# BluetoothAUX.net
KiCad netlist of a schematic drawn in EAGLE
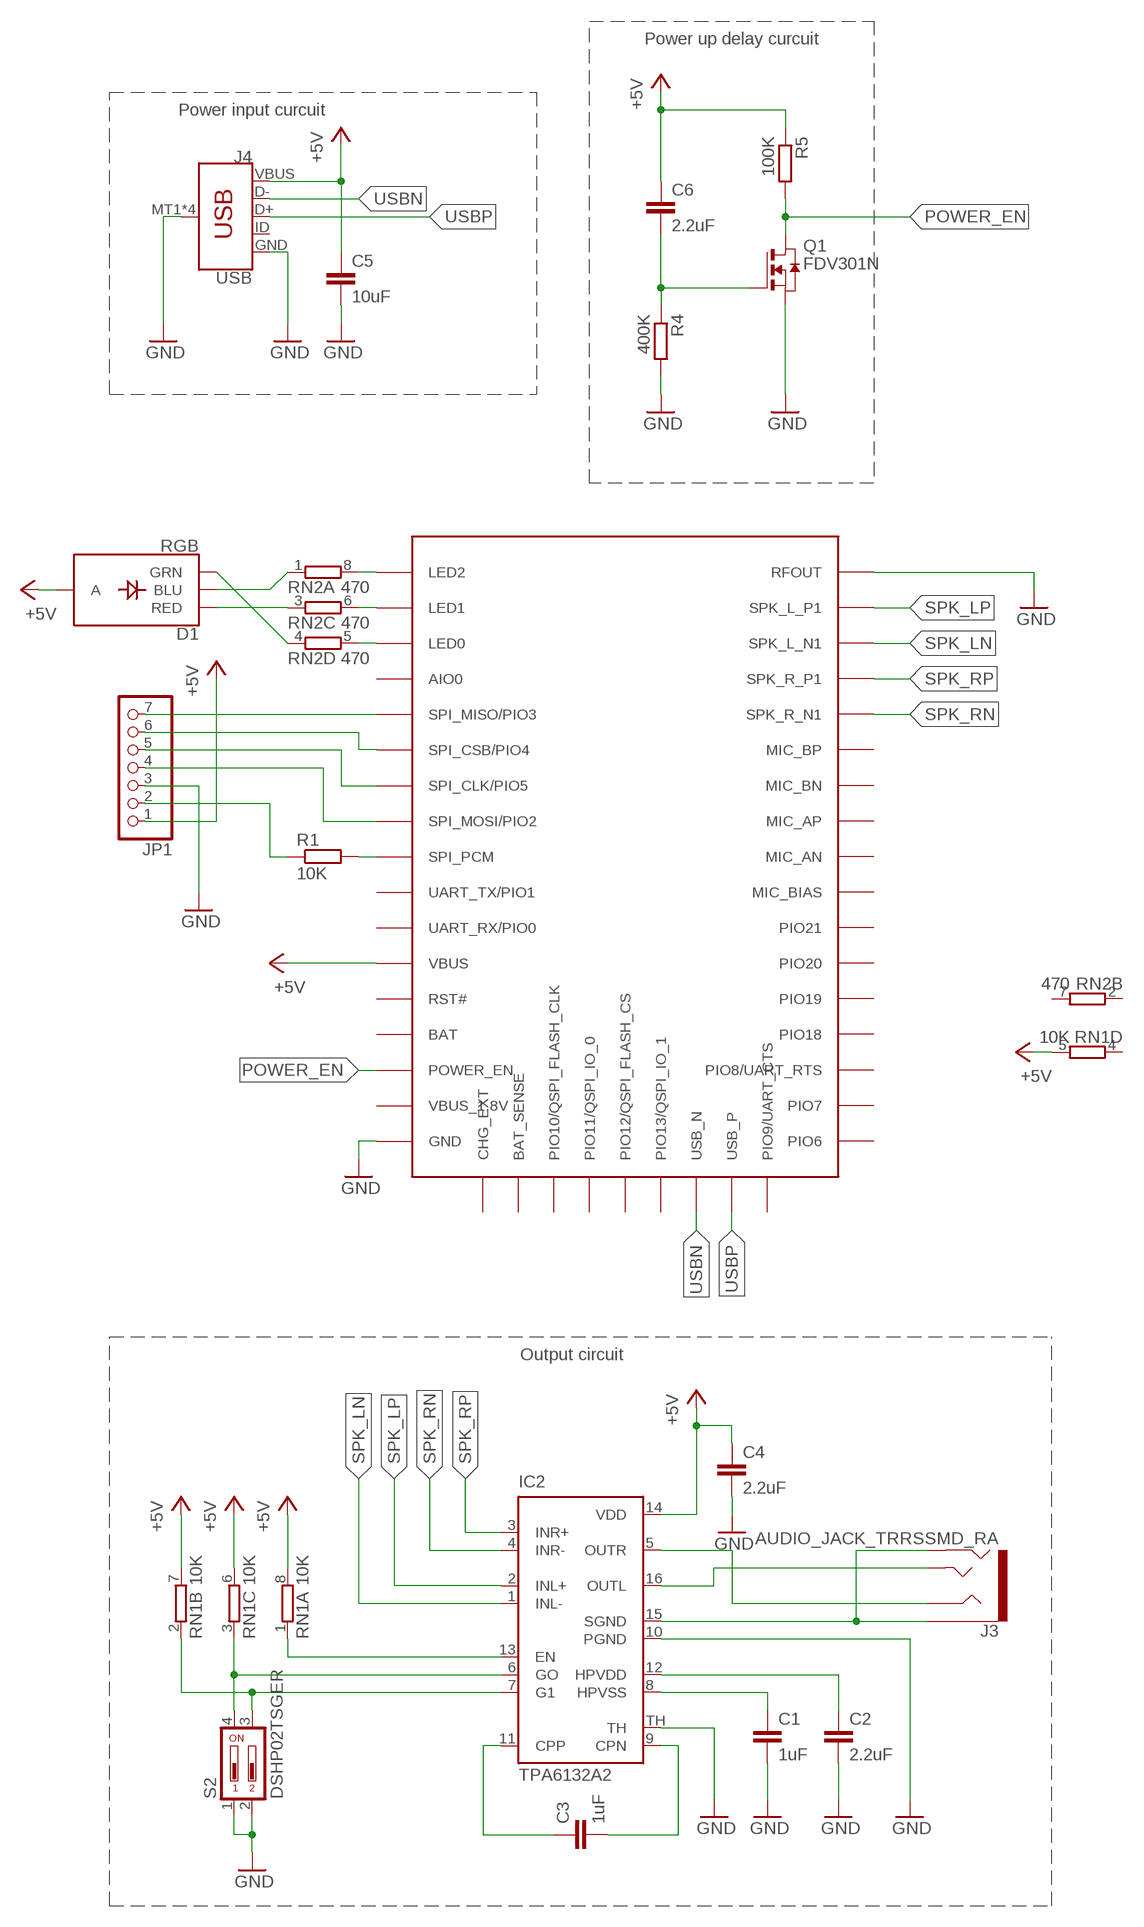
[diagram p0: schematic, sheet 1]

(export (version "E")
  (design (tool "Eeschema 10.0.6"))
  (components
    (comp (ref "C1")
      (value "1uF")
      (footprint "eagle-import:C0603")
      (libsource (lib "eagle-import") (part "resistor_348_C-EUC0603"))
    )
    (comp (ref "C2")
      (value "2.2uF")
      (footprint "eagle-import:C0603")
      (libsource (lib "eagle-import") (part "resistor_348_C-EUC0603"))
    )
    (comp (ref "C3")
      (value "1uF")
      (footprint "eagle-import:C0603")
      (libsource (lib "eagle-import") (part "resistor_348_C-EUC0603"))
    )
    (comp (ref "C4")
      (value "2.2uF")
      (footprint "eagle-import:C0603")
      (libsource (lib "eagle-import") (part "resistor_348_C-EUC0603"))
    )
    (comp (ref "C5")
      (value "10uF")
      (footprint "eagle-import:C1206")
      (libsource (lib "eagle-import") (part "C-EUC1206"))
    )
    (comp (ref "C6")
      (value "2.2uF")
      (footprint "eagle-import:C0603")
      (libsource (lib "eagle-import") (part "resistor_348_C-EUC0603"))
    )
    (comp (ref "D1")
      (value "RGB")
      (footprint "eagle-import:P-LCC-4-3")
      (libsource (lib "eagle-import") (part "LED-RGB-CAPLCC"))
    )
    (comp (ref "IC2")
      (value "TPA6132A2")
      (footprint "eagle-import:QFN16")
      (fields (field (name "MPN") "TPA6132A2RTET"))
      (libsource (lib "eagle-import") (part "TPA6132A2"))
    )
    (comp (ref "J3")
      (value "AUDIO_JACK_TRRSSMD_RA")
      (footprint "eagle-import:AUDIO_JACK_3.5MM_TRRS_SMD_RA")
      (libsource (lib "eagle-import") (part "AUDIO_JACK_TRRSSMD_RA"))
    )
    (comp (ref "J4")
      (value "USB")
      (footprint "eagle-import:USB-MICROB")
      (libsource (lib "eagle-import") (part "USB_MICRO-B_SMT"))
    )
    (comp (ref "JP1")
      (value "PINHD-1X7")
      (footprint "eagle-import:1X07")
      (libsource (lib "eagle-import") (part "PINHD-1X7"))
    )
    (comp (ref "Q1")
      (value "FDV301N")
      (footprint "eagle-import:SOT-23")
      (fields (field (name "MF") "Fairchild Semiconductor"))
      (libsource (lib "eagle-import") (part "FDV301N"))
    )
    (comp (ref "R1")
      (value "10K")
      (footprint "eagle-import:R0603")
      (libsource (lib "eagle-import") (part "R-EU_R0603"))
    )
    (comp (ref "R4")
      (value "400K")
      (footprint "eagle-import:R0603")
      (libsource (lib "eagle-import") (part "R-EU_R0603"))
    )
    (comp (ref "R5")
      (value "100K")
      (footprint "eagle-import:R0603")
      (libsource (lib "eagle-import") (part "R-EU_R0603"))
    )
    (comp (ref "RN1")
      (value "10K")
      (footprint "eagle-import:0603-ARC")
      (libsource (lib "eagle-import") (part "4R-N0603-ARC"))
    )
    (comp (ref "RN2")
      (value "470")
      (footprint "eagle-import:0603-ARC")
      (libsource (lib "eagle-import") (part "4R-N0603-ARC"))
    )
    (comp (ref "S2")
      (value "DSHP02TSGER")
      (footprint "eagle-import:DSHP02TSGER")
      (libsource (lib "eagle-import") (part "DSHP02TSGER"))
    )
    (comp (ref "U$1")
      (value "F3188")
      (footprint "eagle-import:F3188")
      (libsource (lib "eagle-import") (part "F3188"))
    )
  )
  (nets
    (net (code "1") (name "+5V") (class "Default")
      (node (ref "C4") (pin "1") (pinfunction "1_1") (pintype "passive"))
      (node (ref "C5") (pin "1") (pinfunction "1_1") (pintype "passive"))
      (node (ref "C6") (pin "1") (pinfunction "1_1") (pintype "passive"))
      (node (ref "D1") (pin "4") (pinfunction "A_4") (pintype "bidirectional"))
      (node (ref "IC2") (pin "14") (pinfunction "VDD_14") (pintype "power_in"))
      (node (ref "J4") (pin "VBUS") (pinfunction "VBUS_VBUS") (pintype "power_in"))
      (node (ref "JP1") (pin "1") (pinfunction "1_1") (pintype "passive"))
      (node (ref "R5") (pin "1") (pinfunction "1_1") (pintype "passive"))
      (node (ref "RN1") (pin "5") (pinfunction "2_5") (pintype "passive"))
      (node (ref "RN1") (pin "6") (pinfunction "2_6") (pintype "passive"))
      (node (ref "RN1") (pin "7") (pinfunction "2_7") (pintype "passive"))
      (node (ref "RN1") (pin "8") (pinfunction "2_8") (pintype "passive"))
      (node (ref "U$1") (pin "P$12") (pinfunction "VBUS_P$12") (pintype "power_in"))
    )
    (net (code "2") (name "/BAT") (class "Default")
      (node (ref "U$1") (pin "P$14") (pinfunction "BAT_P$14") (pintype "power_in"))
    )
    (net (code "3") (name "/VBUS_1.8V") (class "Default")
      (node (ref "U$1") (pin "P$16") (pinfunction "VBUS_1.8V_P$16") (pintype "power_in"))
    )
    (net (code "4") (name "GND") (class "Default")
      (node (ref "C1") (pin "2") (pinfunction "2_2") (pintype "passive"))
      (node (ref "C2") (pin "2") (pinfunction "2_2") (pintype "passive"))
      (node (ref "C4") (pin "2") (pinfunction "2_2") (pintype "passive"))
      (node (ref "C5") (pin "2") (pinfunction "2_2") (pintype "passive"))
      (node (ref "IC2") (pin "10") (pinfunction "PGND_10") (pintype "power_in"))
      (node (ref "IC2") (pin "TH") (pinfunction "TH_TH") (pintype "passive"))
      (node (ref "J4") (pin "GND") (pinfunction "GND_GND") (pintype "power_in"))
      (node (ref "J4") (pin "MT1") (pinfunction "SHIELD_MT1") (pintype "bidirectional"))
      (node (ref "J4") (pin "MT2") (pinfunction "SHIELD_MT2") (pintype "bidirectional"))
      (node (ref "J4") (pin "P$1") (pinfunction "SHIELD_P$1") (pintype "bidirectional"))
      (node (ref "J4") (pin "P$2") (pinfunction "SHIELD_P$2") (pintype "bidirectional"))
      (node (ref "JP1") (pin "3") (pinfunction "3_3") (pintype "passive"))
      (node (ref "Q1") (pin "P$2") (pinfunction "S_P$2") (pintype "passive"))
      (node (ref "R4") (pin "2") (pinfunction "2_2") (pintype "passive"))
      (node (ref "S2") (pin "1") (pinfunction "1_1") (pintype "passive"))
      (node (ref "S2") (pin "2") (pinfunction "2_2") (pintype "passive"))
      (node (ref "U$1") (pin "P$17") (pinfunction "GND_P$17") (pintype "power_in"))
      (node (ref "U$1") (pin "P$43") (pinfunction "RFOUT_P$43") (pintype "bidirectional"))
    )
    (net (code "5") (name "Net-(D1-BLU)") (class "Default")
      (node (ref "D1") (pin "3") (pinfunction "BLU_3") (pintype "bidirectional"))
      (node (ref "RN2") (pin "1") (pinfunction "1_1") (pintype "passive"))
    )
    (net (code "6") (name "Net-(D1-GRN)") (class "Default")
      (node (ref "D1") (pin "2") (pinfunction "GRN_2") (pintype "bidirectional"))
      (node (ref "RN2") (pin "4") (pinfunction "1_4") (pintype "passive"))
    )
    (net (code "7") (name "Net-(D1-RED)") (class "Default")
      (node (ref "D1") (pin "1") (pinfunction "RED_1") (pintype "bidirectional"))
      (node (ref "RN2") (pin "3") (pinfunction "1_3") (pintype "passive"))
    )
    (net (code "8") (name "Net-(IC2-CPN)") (class "Default")
      (node (ref "C3") (pin "2") (pinfunction "2_2") (pintype "passive"))
      (node (ref "IC2") (pin "9") (pinfunction "CPN_9") (pintype "passive"))
    )
    (net (code "9") (name "Net-(IC2-CPP)") (class "Default")
      (node (ref "C3") (pin "1") (pinfunction "1_1") (pintype "passive"))
      (node (ref "IC2") (pin "11") (pinfunction "CPP_11") (pintype "passive"))
    )
    (net (code "10") (name "Net-(IC2-EN)") (class "Default")
      (node (ref "IC2") (pin "13") (pinfunction "EN_13") (pintype "input"))
      (node (ref "RN1") (pin "1") (pinfunction "1_1") (pintype "passive"))
    )
    (net (code "11") (name "Net-(IC2-G1)") (class "Default")
      (node (ref "IC2") (pin "7") (pinfunction "G1_7") (pintype "input"))
      (node (ref "RN1") (pin "2") (pinfunction "1_2") (pintype "passive"))
      (node (ref "S2") (pin "3") (pinfunction "3_3") (pintype "passive"))
    )
    (net (code "12") (name "Net-(IC2-GO)") (class "Default")
      (node (ref "IC2") (pin "6") (pinfunction "GO_6") (pintype "input"))
      (node (ref "RN1") (pin "3") (pinfunction "1_3") (pintype "passive"))
      (node (ref "S2") (pin "4") (pinfunction "4_4") (pintype "passive"))
    )
    (net (code "13") (name "Net-(IC2-HPVDD)") (class "Default")
      (node (ref "C2") (pin "1") (pinfunction "1_1") (pintype "passive"))
      (node (ref "IC2") (pin "12") (pinfunction "HPVDD_12") (pintype "passive"))
    )
    (net (code "14") (name "Net-(IC2-HPVSS)") (class "Default")
      (node (ref "C1") (pin "1") (pinfunction "1_1") (pintype "passive"))
      (node (ref "IC2") (pin "8") (pinfunction "HPVSS_8") (pintype "passive"))
    )
    (net (code "15") (name "Net-(IC2-OUTL)") (class "Default")
      (node (ref "IC2") (pin "16") (pinfunction "OUTL_16") (pintype "output"))
      (node (ref "J3") (pin "TIP") (pinfunction "TIP_TIP") (pintype "bidirectional"))
    )
    (net (code "16") (name "Net-(IC2-OUTR)") (class "Default")
      (node (ref "IC2") (pin "5") (pinfunction "OUTR_5") (pintype "output"))
      (node (ref "J3") (pin "RING1") (pinfunction "RING1_RING1") (pintype "bidirectional"))
    )
    (net (code "17") (name "Net-(IC2-SGND)") (class "Default")
      (node (ref "IC2") (pin "15") (pinfunction "SGND_15") (pintype "power_in"))
      (node (ref "J3") (pin "EARTH") (pinfunction "EARTH_EARTH") (pintype "bidirectional"))
      (node (ref "J3") (pin "RING2") (pinfunction "RING2_RING2") (pintype "bidirectional"))
    )
    (net (code "18") (name "Net-(JP1-Pad2)") (class "Default")
      (node (ref "JP1") (pin "2") (pinfunction "2_2") (pintype "passive"))
      (node (ref "R1") (pin "1") (pinfunction "1_1") (pintype "passive"))
    )
    (net (code "19") (name "Net-(Q1-G)") (class "Default")
      (node (ref "C6") (pin "2") (pinfunction "2_2") (pintype "passive"))
      (node (ref "Q1") (pin "P$1") (pinfunction "G_P$1") (pintype "passive"))
      (node (ref "R4") (pin "1") (pinfunction "1_1") (pintype "passive"))
    )
    (net (code "20") (name "Net-(RN2A-2)") (class "Default")
      (node (ref "RN2") (pin "8") (pinfunction "2_8") (pintype "passive"))
      (node (ref "U$1") (pin "P$1") (pinfunction "LED2_P$1") (pintype "bidirectional"))
    )
    (net (code "21") (name "Net-(RN2C-2)") (class "Default")
      (node (ref "RN2") (pin "6") (pinfunction "2_6") (pintype "passive"))
      (node (ref "U$1") (pin "P$2") (pinfunction "LED1_P$2") (pintype "bidirectional"))
    )
    (net (code "22") (name "Net-(RN2D-2)") (class "Default")
      (node (ref "RN2") (pin "5") (pinfunction "2_5") (pintype "passive"))
      (node (ref "U$1") (pin "P$3") (pinfunction "LED0_P$3") (pintype "bidirectional"))
    )
    (net (code "23") (name "Net-(U$1-SPI_CLK{slash}PIO5)") (class "Default")
      (node (ref "JP1") (pin "5") (pinfunction "5_5") (pintype "passive"))
      (node (ref "U$1") (pin "P$7") (pinfunction "SPI_CLK/PIO5_P$7") (pintype "bidirectional"))
    )
    (net (code "24") (name "Net-(U$1-SPI_CSB{slash}PIO4)") (class "Default")
      (node (ref "JP1") (pin "6") (pinfunction "6_6") (pintype "passive"))
      (node (ref "U$1") (pin "P$6") (pinfunction "SPI_CSB/PIO4_P$6") (pintype "bidirectional"))
    )
    (net (code "25") (name "Net-(U$1-SPI_MISO{slash}PIO3)") (class "Default")
      (node (ref "JP1") (pin "7") (pinfunction "7_7") (pintype "passive"))
      (node (ref "U$1") (pin "P$5") (pinfunction "SPI_MISO/PIO3_P$5") (pintype "bidirectional"))
    )
    (net (code "26") (name "Net-(U$1-SPI_MOSI{slash}PIO2)") (class "Default")
      (node (ref "JP1") (pin "4") (pinfunction "4_4") (pintype "passive"))
      (node (ref "U$1") (pin "P$8") (pinfunction "SPI_MOSI/PIO2_P$8") (pintype "bidirectional"))
    )
    (net (code "27") (name "Net-(U$1-SPI_PCM)") (class "Default")
      (node (ref "R1") (pin "2") (pinfunction "2_2") (pintype "passive"))
      (node (ref "U$1") (pin "P$9") (pinfunction "SPI_PCM_P$9") (pintype "bidirectional"))
    )
    (net (code "28") (name "POWER_EN") (class "Default")
      (node (ref "Q1") (pin "P$3") (pinfunction "D_P$3") (pintype "passive"))
      (node (ref "R5") (pin "2") (pinfunction "2_2") (pintype "passive"))
      (node (ref "U$1") (pin "P$15") (pinfunction "POWER_EN_P$15") (pintype "bidirectional"))
    )
    (net (code "29") (name "SPK_LN") (class "Default")
      (node (ref "IC2") (pin "1") (pinfunction "INL-_1") (pintype "input"))
      (node (ref "U$1") (pin "P$41") (pinfunction "SPK_L_N1_P$41") (pintype "bidirectional"))
    )
    (net (code "30") (name "SPK_LP") (class "Default")
      (node (ref "IC2") (pin "2") (pinfunction "INL+_2") (pintype "input"))
      (node (ref "U$1") (pin "P$42") (pinfunction "SPK_L_P1_P$42") (pintype "bidirectional"))
    )
    (net (code "31") (name "SPK_RN") (class "Default")
      (node (ref "IC2") (pin "4") (pinfunction "INR-_4") (pintype "input"))
      (node (ref "U$1") (pin "P$39") (pinfunction "SPK_R_N1_P$39") (pintype "bidirectional"))
    )
    (net (code "32") (name "SPK_RP") (class "Default")
      (node (ref "IC2") (pin "3") (pinfunction "INR+_3") (pintype "input"))
      (node (ref "U$1") (pin "P$40") (pinfunction "SPK_R_P1_P$40") (pintype "bidirectional"))
    )
    (net (code "33") (name "USBN") (class "Default")
      (node (ref "J4") (pin "D-") (pinfunction "D-_D-") (pintype "bidirectional"))
      (node (ref "U$1") (pin "P$24") (pinfunction "USB_N_P$24") (pintype "bidirectional"))
    )
    (net (code "34") (name "USBP") (class "Default")
      (node (ref "J4") (pin "D+") (pinfunction "D+_D+") (pintype "bidirectional"))
      (node (ref "U$1") (pin "P$25") (pinfunction "USB_P_P$25") (pintype "bidirectional"))
    )
    (net (code "35") (name "unconnected-(J4-PadID)") (class "Default")
      (node (ref "J4") (pin "ID") (pinfunction "ID_ID") (pintype "bidirectional"))
    )
    (net (code "36") (name "unconnected-(RN1D-1-Pad4)") (class "Default")
      (node (ref "RN1") (pin "4") (pinfunction "1_4") (pintype "passive"))
    )
    (net (code "37") (name "unconnected-(RN2B-1-Pad2)") (class "Default")
      (node (ref "RN2") (pin "2") (pinfunction "1_2") (pintype "passive"))
    )
    (net (code "38") (name "unconnected-(RN2B-2-Pad7)") (class "Default")
      (node (ref "RN2") (pin "7") (pinfunction "2_7") (pintype "passive"))
    )
    (net (code "39") (name "unconnected-(U$1-AIO0-PadP$4)") (class "Default")
      (node (ref "U$1") (pin "P$4") (pinfunction "AIO0_P$4") (pintype "bidirectional"))
    )
    (net (code "40") (name "unconnected-(U$1-BAT_SENSE-PadP$19)") (class "Default")
      (node (ref "U$1") (pin "P$19") (pinfunction "BAT_SENSE_P$19") (pintype "bidirectional"))
    )
    (net (code "41") (name "unconnected-(U$1-CHG_EXT-PadP$18)") (class "Default")
      (node (ref "U$1") (pin "P$18") (pinfunction "CHG_EXT_P$18") (pintype "bidirectional"))
    )
    (net (code "42") (name "unconnected-(U$1-MIC_AN-PadP$35)") (class "Default")
      (node (ref "U$1") (pin "P$35") (pinfunction "MIC_AN_P$35") (pintype "bidirectional"))
    )
    (net (code "43") (name "unconnected-(U$1-MIC_AP-PadP$36)") (class "Default")
      (node (ref "U$1") (pin "P$36") (pinfunction "MIC_AP_P$36") (pintype "bidirectional"))
    )
    (net (code "44") (name "unconnected-(U$1-MIC_BIAS-PadP$34)") (class "Default")
      (node (ref "U$1") (pin "P$34") (pinfunction "MIC_BIAS_P$34") (pintype "bidirectional"))
    )
    (net (code "45") (name "unconnected-(U$1-MIC_BN-PadP$37)") (class "Default")
      (node (ref "U$1") (pin "P$37") (pinfunction "MIC_BN_P$37") (pintype "bidirectional"))
    )
    (net (code "46") (name "unconnected-(U$1-MIC_BP-PadP$38)") (class "Default")
      (node (ref "U$1") (pin "P$38") (pinfunction "MIC_BP_P$38") (pintype "bidirectional"))
    )
    (net (code "47") (name "unconnected-(U$1-PIO6-PadP$27)") (class "Default")
      (node (ref "U$1") (pin "P$27") (pinfunction "PIO6_P$27") (pintype "bidirectional"))
    )
    (net (code "48") (name "unconnected-(U$1-PIO7-PadP$28)") (class "Default")
      (node (ref "U$1") (pin "P$28") (pinfunction "PIO7_P$28") (pintype "bidirectional"))
    )
    (net (code "49") (name "unconnected-(U$1-PIO8{slash}UART_RTS-PadP$29)") (class "Default")
      (node (ref "U$1") (pin "P$29") (pinfunction "PIO8/UART_RTS_P$29") (pintype "bidirectional"))
    )
    (net (code "50") (name "unconnected-(U$1-PIO9{slash}UART_CTS-PadP$26)") (class "Default")
      (node (ref "U$1") (pin "P$26") (pinfunction "PIO9/UART_CTS_P$26") (pintype "bidirectional"))
    )
    (net (code "51") (name "unconnected-(U$1-PIO10{slash}QSPI_FLASH_CLK-PadP$20)") (class "Default")
      (node (ref "U$1") (pin "P$20") (pinfunction "PIO10/QSPI_FLASH_CLK_P$20") (pintype "bidirectional"))
    )
    (net (code "52") (name "unconnected-(U$1-PIO11{slash}QSPI_IO_0-PadP$21)") (class "Default")
      (node (ref "U$1") (pin "P$21") (pinfunction "PIO11/QSPI_IO_0_P$21") (pintype "bidirectional"))
    )
    (net (code "53") (name "unconnected-(U$1-PIO12{slash}QSPI_FLASH_CS-PadP$22)") (class "Default")
      (node (ref "U$1") (pin "P$22") (pinfunction "PIO12/QSPI_FLASH_CS_P$22") (pintype "bidirectional"))
    )
    (net (code "54") (name "unconnected-(U$1-PIO13{slash}QSPI_IO_1-PadP$23)") (class "Default")
      (node (ref "U$1") (pin "P$23") (pinfunction "PIO13/QSPI_IO_1_P$23") (pintype "bidirectional"))
    )
    (net (code "55") (name "unconnected-(U$1-PIO18-PadP$30)") (class "Default")
      (node (ref "U$1") (pin "P$30") (pinfunction "PIO18_P$30") (pintype "bidirectional"))
    )
    (net (code "56") (name "unconnected-(U$1-PIO19-PadP$31)") (class "Default")
      (node (ref "U$1") (pin "P$31") (pinfunction "PIO19_P$31") (pintype "bidirectional"))
    )
    (net (code "57") (name "unconnected-(U$1-PIO20-PadP$32)") (class "Default")
      (node (ref "U$1") (pin "P$32") (pinfunction "PIO20_P$32") (pintype "bidirectional"))
    )
    (net (code "58") (name "unconnected-(U$1-PIO21-PadP$33)") (class "Default")
      (node (ref "U$1") (pin "P$33") (pinfunction "PIO21_P$33") (pintype "bidirectional"))
    )
    (net (code "59") (name "unconnected-(U$1-RST#-PadP$13)") (class "Default")
      (node (ref "U$1") (pin "P$13") (pinfunction "RST#_P$13") (pintype "bidirectional"))
    )
    (net (code "60") (name "unconnected-(U$1-UART_RX{slash}PIO0-PadP$11)") (class "Default")
      (node (ref "U$1") (pin "P$11") (pinfunction "UART_RX/PIO0_P$11") (pintype "bidirectional"))
    )
    (net (code "61") (name "unconnected-(U$1-UART_TX{slash}PIO1-PadP$10)") (class "Default")
      (node (ref "U$1") (pin "P$10") (pinfunction "UART_TX/PIO1_P$10") (pintype "bidirectional"))
    )
  )
)
